# Flight_Track_V2.net
KiCad netlist of a schematic drawn in EasyEDA Pro
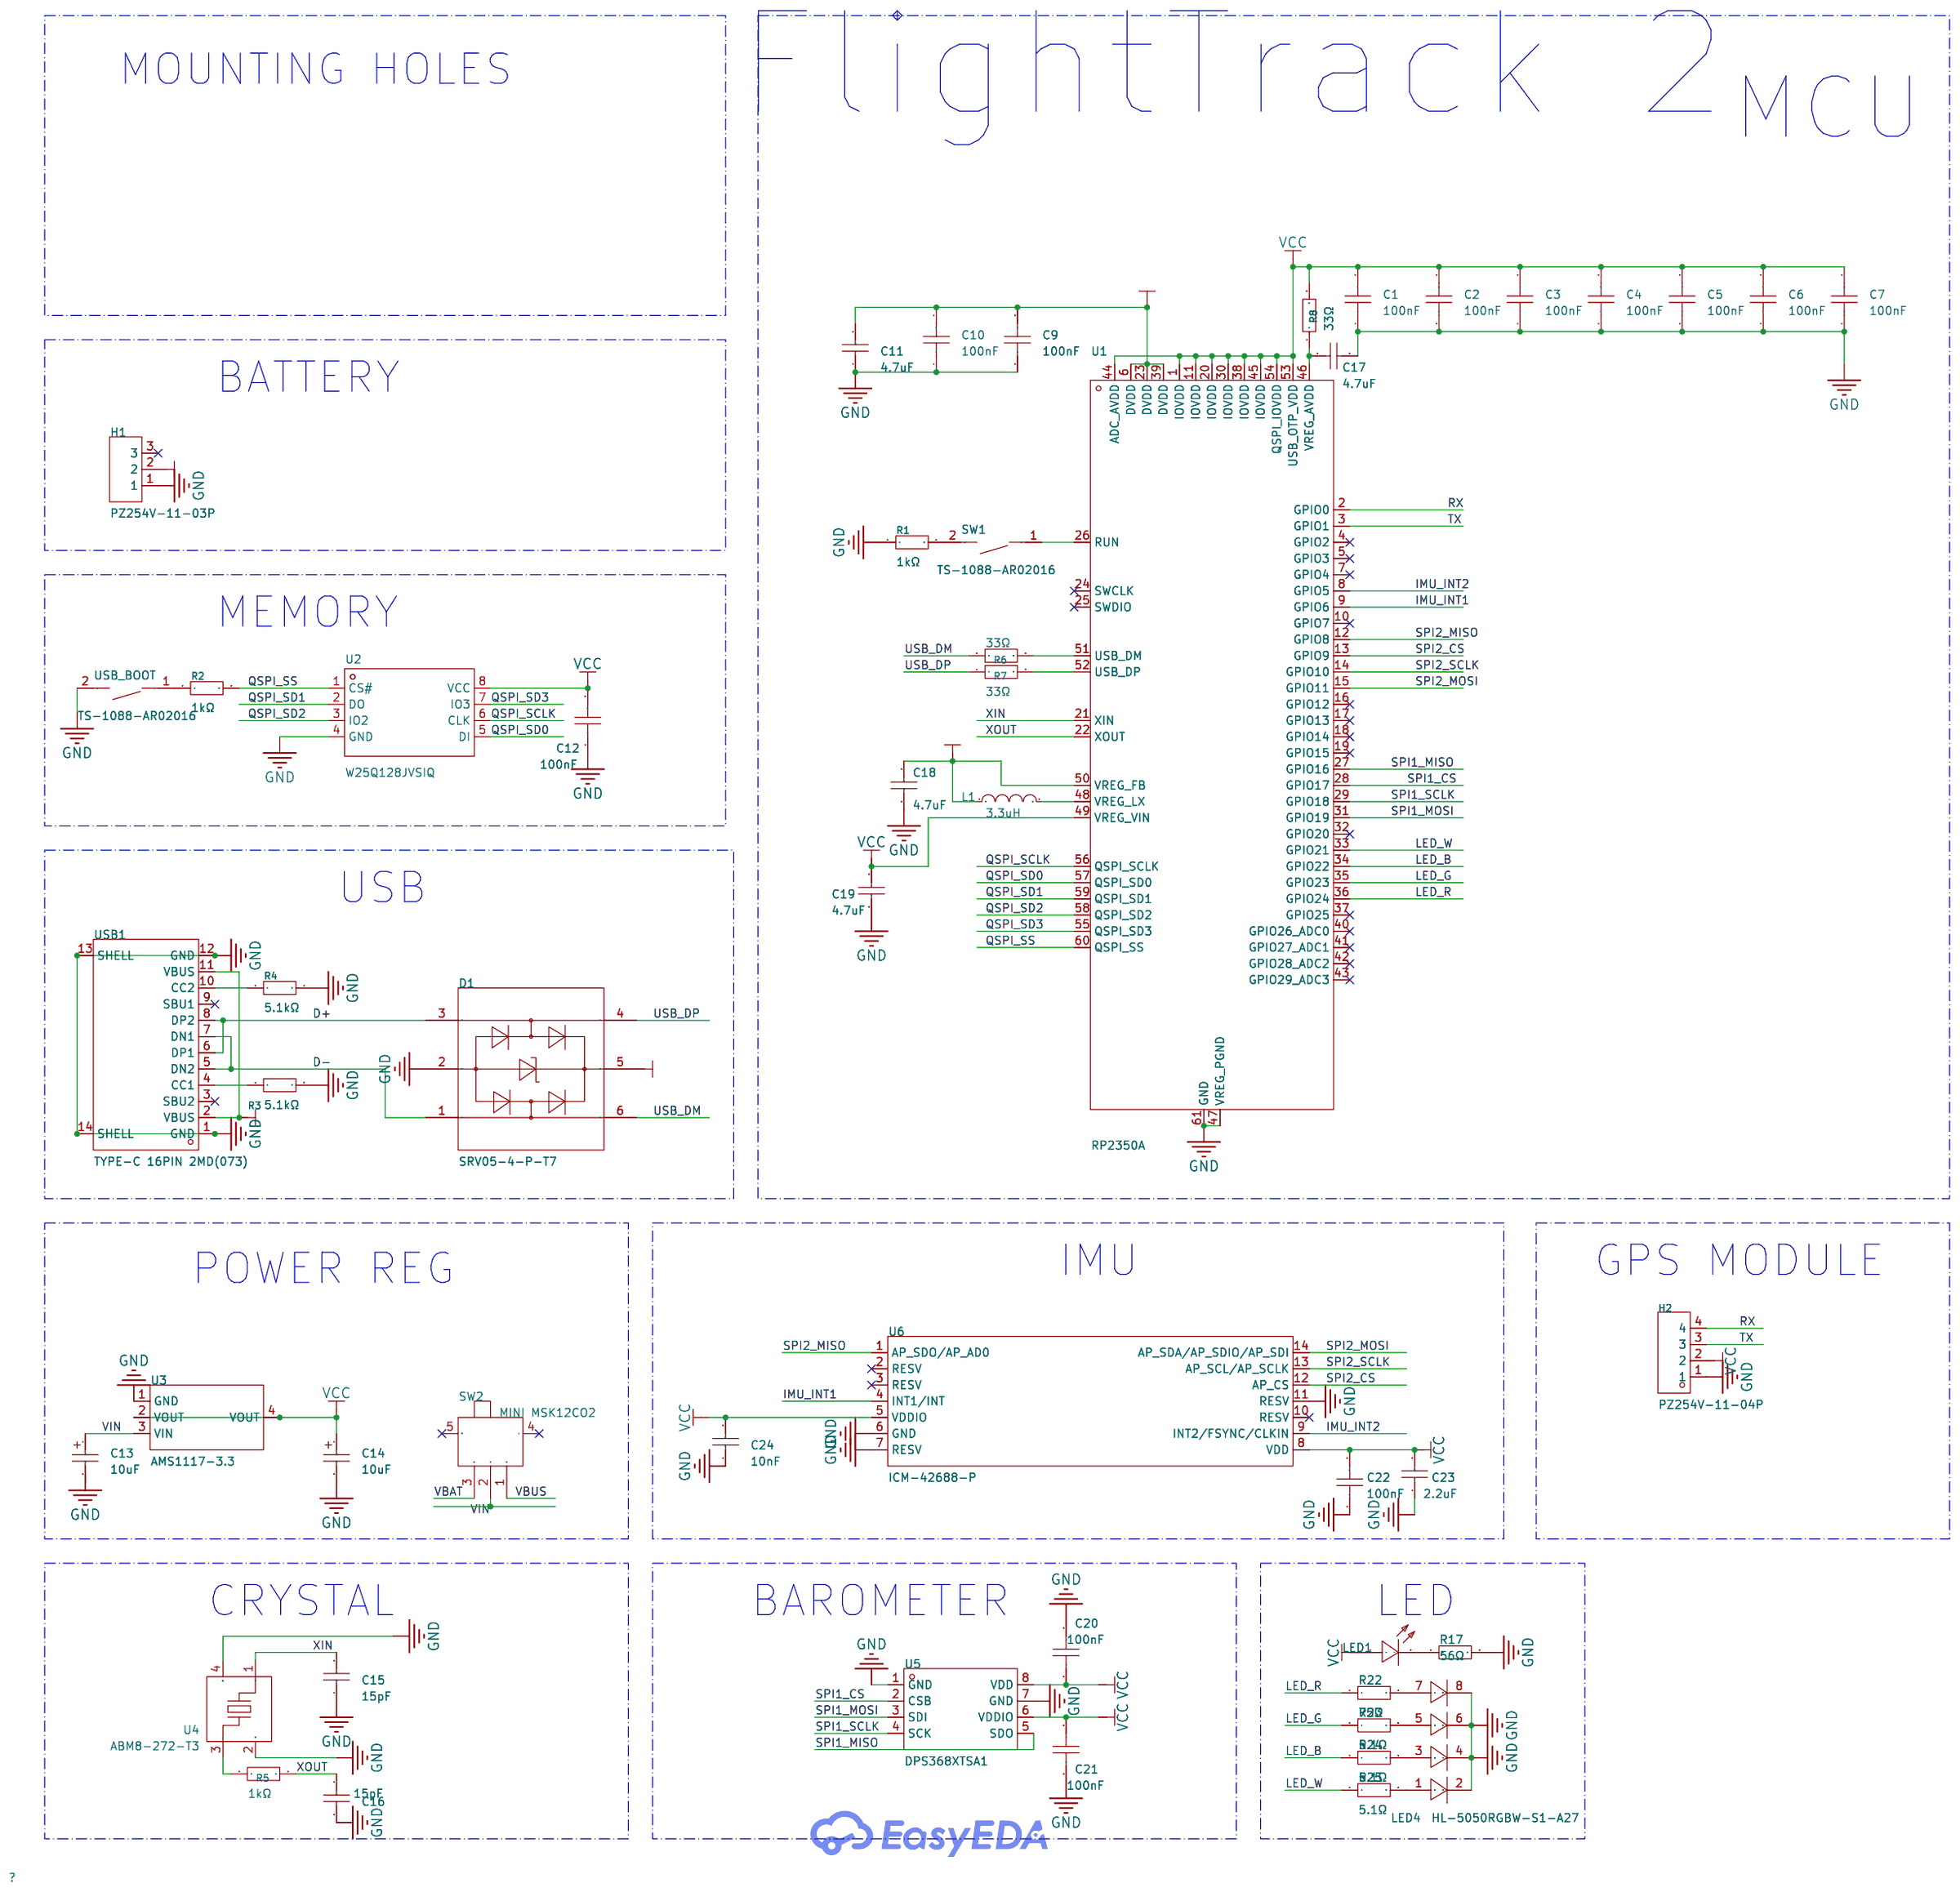
[diagram p0: schematic sheet]

(export (version "E")
  (design (tool "Eeschema 10.0.6"))
  (components
    (comp (ref "C1")
      (value "100nF")
      (footprint "easyedapro:C0402")
      (fields
        (field (name "Manufacturer Part") "CL05B104KO5NNNC")
        (field (name "Manufacturer") "SAMSUNG(三星)")
      )
      (libsource (lib "easyedapro") (part "CL05B104KO5NNNC"))
    )
    (comp (ref "C2")
      (value "100nF")
      (footprint "easyedapro:C0402")
      (fields
        (field (name "Manufacturer Part") "CL05B104KO5NNNC")
        (field (name "Manufacturer") "SAMSUNG(三星)")
      )
      (libsource (lib "easyedapro") (part "CL05B104KO5NNNC"))
    )
    (comp (ref "C3")
      (value "100nF")
      (footprint "easyedapro:C0402")
      (fields
        (field (name "Manufacturer Part") "CL05B104KO5NNNC")
        (field (name "Manufacturer") "SAMSUNG(三星)")
      )
      (libsource (lib "easyedapro") (part "CL05B104KO5NNNC"))
    )
    (comp (ref "C4")
      (value "100nF")
      (footprint "easyedapro:C0402")
      (fields
        (field (name "Manufacturer Part") "CL05B104KO5NNNC")
        (field (name "Manufacturer") "SAMSUNG(三星)")
      )
      (libsource (lib "easyedapro") (part "CL05B104KO5NNNC"))
    )
    (comp (ref "C5")
      (value "100nF")
      (footprint "easyedapro:C0402")
      (fields
        (field (name "Manufacturer Part") "CL05B104KO5NNNC")
        (field (name "Manufacturer") "SAMSUNG(三星)")
      )
      (libsource (lib "easyedapro") (part "CL05B104KO5NNNC"))
    )
    (comp (ref "C6")
      (value "100nF")
      (footprint "easyedapro:C0402")
      (fields
        (field (name "Manufacturer Part") "CL05B104KO5NNNC")
        (field (name "Manufacturer") "SAMSUNG(三星)")
      )
      (libsource (lib "easyedapro") (part "CL05B104KO5NNNC"))
    )
    (comp (ref "C7")
      (value "100nF")
      (footprint "easyedapro:C0402")
      (fields
        (field (name "Manufacturer Part") "CL05B104KO5NNNC")
        (field (name "Manufacturer") "SAMSUNG(三星)")
      )
      (libsource (lib "easyedapro") (part "CL05B104KO5NNNC"))
    )
    (comp (ref "C9")
      (value "100nF")
      (footprint "easyedapro:C0402")
      (fields
        (field (name "Manufacturer Part") "CL05B104KO5NNNC")
        (field (name "Manufacturer") "SAMSUNG(三星)")
      )
      (libsource (lib "easyedapro") (part "CL05B104KO5NNNC"))
    )
    (comp (ref "C10")
      (value "100nF")
      (footprint "easyedapro:C0402")
      (fields
        (field (name "Manufacturer Part") "CL05B104KO5NNNC")
        (field (name "Manufacturer") "SAMSUNG(三星)")
      )
      (libsource (lib "easyedapro") (part "CL05B104KO5NNNC"))
    )
    (comp (ref "C11")
      (value "4.7uF")
      (footprint "easyedapro:C0805")
      (fields
        (field (name "Manufacturer Part") "CL21A475KAQNNNE")
        (field (name "Manufacturer") "SAMSUNG(三星)")
      )
      (libsource (lib "easyedapro") (part "CL21A475KAQNNNE"))
    )
    (comp (ref "C12")
      (value "100nF")
      (footprint "easyedapro:C0603")
      (description "Capacitance:100nF Tolerance:±10% Tolerance:±10% Voltage Rating:50V Temperature Coefficient:X7R")
      (fields
        (field (name "Manufacturer Part") "CC0603KRX7R9BB104")
        (field (name "Manufacturer") "YAGEO(国巨)")
      )
      (libsource (lib "easyedapro") (part "CC0603KRX7R9BB104"))
    )
    (comp (ref "C13")
      (value "10uF")
      (footprint "easyedapro:CAP-SMD_L3.2-W1.6-RD-C7171")
      (fields (field (name "Manufacturer Part") "TAJA106K016RNJ") (field (name "Manufacturer") "Kyocera AVX"))
      (libsource (lib "easyedapro") (part "TAJA106K016RNJ"))
    )
    (comp (ref "C14")
      (value "10uF")
      (footprint "easyedapro:CAP-SMD_L3.2-W1.6-RD-C7171")
      (fields (field (name "Manufacturer Part") "TAJA106K016RNJ") (field (name "Manufacturer") "Kyocera AVX"))
      (libsource (lib "easyedapro") (part "TAJA106K016RNJ"))
    )
    (comp (ref "C15")
      (value "15pF")
      (footprint "easyedapro:C0402")
      (fields (field (name "Manufacturer Part") "0402CG150J500NT") (field (name "Manufacturer") "FH(风华)"))
      (libsource (lib "easyedapro") (part "0402CG150J500NT"))
    )
    (comp (ref "C16")
      (value "15pF")
      (footprint "easyedapro:C0402")
      (fields (field (name "Manufacturer Part") "0402CG150J500NT") (field (name "Manufacturer") "FH(风华)"))
      (libsource (lib "easyedapro") (part "0402CG150J500NT"))
    )
    (comp (ref "C17")
      (value "4.7uF")
      (footprint "easyedapro:C0805")
      (fields
        (field (name "Manufacturer Part") "CL21A475KAQNNNE")
        (field (name "Manufacturer") "SAMSUNG(三星)")
      )
      (libsource (lib "easyedapro") (part "CL21A475KAQNNNE"))
    )
    (comp (ref "C18")
      (value "4.7uF")
      (footprint "easyedapro:C0805")
      (fields
        (field (name "Manufacturer Part") "CL21A475KAQNNNE")
        (field (name "Manufacturer") "SAMSUNG(三星)")
      )
      (libsource (lib "easyedapro") (part "CL21A475KAQNNNE"))
    )
    (comp (ref "C19")
      (value "4.7uF")
      (footprint "easyedapro:C0805")
      (fields
        (field (name "Manufacturer Part") "CL21A475KAQNNNE")
        (field (name "Manufacturer") "SAMSUNG(三星)")
      )
      (libsource (lib "easyedapro") (part "CL21A475KAQNNNE"))
    )
    (comp (ref "C20")
      (value "100nF")
      (footprint "easyedapro:C0402")
      (fields
        (field (name "Manufacturer Part") "CL05B104KO5NNNC")
        (field (name "Manufacturer") "SAMSUNG(三星)")
      )
      (libsource (lib "easyedapro") (part "CL05B104KO5NNNC"))
    )
    (comp (ref "C21")
      (value "100nF")
      (footprint "easyedapro:C0402")
      (fields
        (field (name "Manufacturer Part") "CL05B104KO5NNNC")
        (field (name "Manufacturer") "SAMSUNG(三星)")
      )
      (libsource (lib "easyedapro") (part "CL05B104KO5NNNC"))
    )
    (comp (ref "C22")
      (value "100nF")
      (footprint "easyedapro:C0402")
      (fields
        (field (name "Manufacturer Part") "CL05B104KO5NNNC")
        (field (name "Manufacturer") "SAMSUNG(三星)")
      )
      (libsource (lib "easyedapro") (part "CL05B104KO5NNNC"))
    )
    (comp (ref "C23")
      (value "2.2uF")
      (footprint "easyedapro:C0603")
      (fields
        (field (name "Manufacturer Part") "CL10A225KO8NNNC")
        (field (name "Manufacturer") "SAMSUNG(三星)")
      )
      (libsource (lib "easyedapro") (part "CL10A225KO8NNNC"))
    )
    (comp (ref "C24")
      (value "10nF")
      (footprint "easyedapro:C0402")
      (fields
        (field (name "Manufacturer Part") "CL05B103KB5NNNC")
        (field (name "Manufacturer") "SAMSUNG(三星)")
      )
      (libsource (lib "easyedapro") (part "CL05B103KB5NNNC"))
    )
    (comp (ref "D1")
      (value "SRV05-4-P-T7")
      (footprint "easyedapro:SOT-23-6_L2.9-W1.6-P0.95-LS2.8-BL")
      (fields (field (name "Manufacturer") "TECH PUBLIC(台舟)"))
      (libsource (lib "easyedapro") (part "USBLC6-2SC6"))
    )
    (comp (ref "H1")
      (value "PZ254V-11-03P")
      (footprint "easyedapro:HDR-TH_3P-P2.54-V-M")
      (fields (field (name "Manufacturer") "XFCN(兴飞)"))
      (libsource (lib "easyedapro") (part "PZ254V-11-03P_C2937625"))
    )
    (comp (ref "H2")
      (value "PZ254V-11-04P")
      (footprint "easyedapro:HDR-TH_4P-P2.54-V-M")
      (fields (field (name "Manufacturer") "XFCN(兴飞)"))
      (libsource (lib "easyedapro") (part "PZ254V-11-04P_C2691448"))
    )
    (comp (ref "L1")
      (value "3.3uH")
      (footprint "easyedapro:L0603")
      (fields (field (name "Manufacturer Part") "CMI160808U3R3KT") (field (name "Manufacturer") "FH(风华)"))
      (libsource (lib "easyedapro") (part "CMI160808U3R3KT"))
    )
    (comp (ref "LED1")
      (value "NCD0805R1")
      (footprint "easyedapro:LED0805-R-RD")
      (fields (field (name "Manufacturer") "国星光电"))
      (libsource (lib "easyedapro") (part "FC-2012HRK-620D"))
    )
    (comp (ref "LED4")
      (value "HL-5050RGBW-S1-A27")
      (footprint "easyedapro:LED-SMD_8P-L5.0-W5.0-P1.20_HL-5050RGBW-S1-A27")
      (fields (field (name "Manufacturer") "HONGLITRONIC(鸿利光电)"))
      (libsource (lib "easyedapro") (part "HL-5050RGBW-S1-A27"))
    )
    (comp (ref "R1")
      (value "1kΩ")
      (footprint "easyedapro:R0402")
      (fields
        (field (name "Manufacturer Part") "0402WGF1001TCE")
        (field (name "Manufacturer") "UNI-ROYAL(厚声)")
      )
      (libsource (lib "easyedapro") (part "0402WGF1001TCE"))
    )
    (comp (ref "R2")
      (value "1kΩ")
      (footprint "easyedapro:R0402")
      (fields
        (field (name "Manufacturer Part") "0402WGF1001TCE")
        (field (name "Manufacturer") "UNI-ROYAL(厚声)")
      )
      (libsource (lib "easyedapro") (part "0402WGF1001TCE"))
    )
    (comp (ref "R3")
      (value "5.1kΩ")
      (footprint "easyedapro:R0402")
      (fields
        (field (name "Manufacturer Part") "0402WGF5101TCE")
        (field (name "Manufacturer") "UNI-ROYAL(厚声)")
      )
      (libsource (lib "easyedapro") (part "0402WGF5101TCE"))
    )
    (comp (ref "R4")
      (value "5.1kΩ")
      (footprint "easyedapro:R0402")
      (fields
        (field (name "Manufacturer Part") "0402WGF5101TCE")
        (field (name "Manufacturer") "UNI-ROYAL(厚声)")
      )
      (libsource (lib "easyedapro") (part "0402WGF5101TCE"))
    )
    (comp (ref "R5")
      (value "1kΩ")
      (footprint "easyedapro:R0402")
      (fields
        (field (name "Manufacturer Part") "0402WGF1001TCE")
        (field (name "Manufacturer") "UNI-ROYAL(厚声)")
      )
      (libsource (lib "easyedapro") (part "0402WGF1001TCE"))
    )
    (comp (ref "R6")
      (value "33Ω")
      (footprint "easyedapro:R0402")
      (fields
        (field (name "Manufacturer Part") "0402WGF330JTCE")
        (field (name "Manufacturer") "UNI-ROYAL(厚声)")
      )
      (libsource (lib "easyedapro") (part "0402WGF330JTCE"))
    )
    (comp (ref "R7")
      (value "33Ω")
      (footprint "easyedapro:R0402")
      (fields
        (field (name "Manufacturer Part") "0402WGF330JTCE")
        (field (name "Manufacturer") "UNI-ROYAL(厚声)")
      )
      (libsource (lib "easyedapro") (part "0402WGF330JTCE"))
    )
    (comp (ref "R8")
      (value "33Ω")
      (footprint "easyedapro:R0402")
      (fields
        (field (name "Manufacturer Part") "0402WGF330JTCE")
        (field (name "Manufacturer") "UNI-ROYAL(厚声)")
      )
      (libsource (lib "easyedapro") (part "0402WGF330JTCE"))
    )
    (comp (ref "R17")
      (value "56Ω")
      (footprint "easyedapro:R0603")
      (fields
        (field (name "Manufacturer Part") "0603WAF560JT5E")
        (field (name "Manufacturer") "UNI-ROYAL(厚声)")
      )
      (libsource (lib "easyedapro") (part "0603WAF560JT5E"))
    )
    (comp (ref "R22")
      (value "75Ω")
      (footprint "easyedapro:R0603")
      (fields
        (field (name "Manufacturer Part") "0603WAF750JT5E")
        (field (name "Manufacturer") "UNI-ROYAL(厚声)")
      )
      (libsource (lib "easyedapro") (part "0603WAF750JT5E"))
    )
    (comp (ref "R23")
      (value "5.1Ω")
      (footprint "easyedapro:R0603")
      (fields
        (field (name "Manufacturer Part") "0603WAF510KT5E")
        (field (name "Manufacturer") "UNI-ROYAL(厚声)")
      )
      (libsource (lib "easyedapro") (part "0603WAF510KT5E"))
    )
    (comp (ref "R24")
      (value "5.1Ω")
      (footprint "easyedapro:R0603")
      (fields
        (field (name "Manufacturer Part") "0603WAF510KT5E")
        (field (name "Manufacturer") "UNI-ROYAL(厚声)")
      )
      (libsource (lib "easyedapro") (part "0603WAF510KT5E"))
    )
    (comp (ref "R25")
      (value "5.1Ω")
      (footprint "easyedapro:R0603")
      (fields
        (field (name "Manufacturer Part") "0603WAF510KT5E")
        (field (name "Manufacturer") "UNI-ROYAL(厚声)")
      )
      (libsource (lib "easyedapro") (part "0603WAF510KT5E"))
    )
    (comp (ref "SW1")
      (value "TS-1088-AR02016")
      (footprint "easyedapro:SW-SMD_L3.9-W3.0-P4.45")
      (fields (field (name "Manufacturer") "XUNPU(讯普)"))
      (libsource (lib "easyedapro") (part "TS-1088-AR02016"))
    )
    (comp (ref "SW2")
      (value "MINI MSK12CO2")
      (footprint "easyedapro:SW-SMD_MSK12CO2")
      (fields (field (name "Manufacturer") "SHOU HAN(首韩)"))
      (libsource (lib "easyedapro") (part "MINI MSK12CO2"))
    )
    (comp (ref "U1")
      (value "RP2350A")
      (footprint "easyedapro:QFN-60_L7.0-W7.0-P0.40-TL-EP3.4")
      (fields (field (name "Manufacturer") "Raspberry Pi(树莓派)"))
      (libsource (lib "easyedapro") (part "RP2350A_C42411118"))
    )
    (comp (ref "U2")
      (value "W25Q128JVSIQ")
      (footprint "easyedapro:SOIC-8_L5.3-W5.3-P1.27-LS8.0-BL")
      (fields (field (name "Manufacturer") "WINBOND(华邦)"))
      (libsource (lib "easyedapro") (part "W25Q128JVSIQTR"))
    )
    (comp (ref "U3")
      (value "AMS1117-3.3")
      (footprint "easyedapro:SOT-223-3_L6.5-W3.4-P2.30-LS7.0-BR")
      (fields (field (name "Manufacturer") "AMS"))
      (libsource (lib "easyedapro") (part "AMS1117-3.3"))
    )
    (comp (ref "U4")
      (value "ABM8-272-T3")
      (footprint "easyedapro:CRYSTAL-SMD_4P-L3.2-W2.5-BL")
      (fields (field (name "Manufacturer") "ABRACON"))
      (libsource (lib "easyedapro") (part "ABM8-272-T3_C20625731"))
    )
    (comp (ref "U5")
      (value "DPS368XTSA1")
      (footprint "easyedapro:LGA-8_L2.5-W2.0-P0.65-TR_DPS368")
      (fields (field (name "Manufacturer") "Infineon(英飞凌)"))
      (libsource (lib "easyedapro") (part "DPS368XTSA1"))
    )
    (comp (ref "U6")
      (value "ICM-42688-P")
      (footprint "easyedapro:LGA-14_L3.0-W2.5-P0.50-TL")
      (description "Sensor Type:Accelerometer gyroscope")
      (fields (field (name "Manufacturer") "TDK InvenSense(应美盛)"))
      (libsource (lib "easyedapro") (part "ICM-42688-P"))
    )
    (comp (ref "USB1")
      (value "TYPE-C 16PIN 2MD(073)")
      (footprint "easyedapro:USB-C-SMD_TYPE-C-6PIN-2MD-073")
      (fields (field (name "Manufacturer") "SHOU HAN(首韩)"))
      (libsource (lib "easyedapro") (part "TYPE-C 16PIN 2MD(073)"))
    )
    (comp (ref "USB_BOOT")
      (value "TS-1088-AR02016")
      (footprint "easyedapro:SW-SMD_L3.9-W3.0-P4.45")
      (fields (field (name "Manufacturer") "XUNPU(讯普)"))
      (libsource (lib "easyedapro") (part "TS-1088-AR02016"))
    )
  )
  (nets
    (net (code "1") (name "/D+") (class "Default")
      (node (ref "D1") (pin "3") (pinfunction "3_3") (pintype "input"))
      (node (ref "USB1") (pin "6") (pinfunction "DP1_6") (pintype "unspecified"))
      (node (ref "USB1") (pin "8") (pinfunction "DP2_8") (pintype "unspecified"))
    )
    (net (code "2") (name "/D-") (class "Default")
      (node (ref "D1") (pin "1") (pinfunction "1_1") (pintype "input"))
      (node (ref "USB1") (pin "5") (pinfunction "DN2_5") (pintype "unspecified"))
      (node (ref "USB1") (pin "7") (pinfunction "DN1_7") (pintype "unspecified"))
    )
    (net (code "3") (name "/IMU_INT1") (class "Default")
      (node (ref "U1") (pin "9") (pinfunction "GPIO6_9") (pintype "unspecified"))
      (node (ref "U6") (pin "4") (pinfunction "INT1/INT_4") (pintype "unspecified"))
    )
    (net (code "4") (name "/IMU_INT2") (class "Default")
      (node (ref "U1") (pin "8") (pinfunction "GPIO5_8") (pintype "unspecified"))
      (node (ref "U6") (pin "9") (pinfunction "INT2/FSYNC/CLKIN_9") (pintype "unspecified"))
    )
    (net (code "5") (name "/LED_B") (class "Default")
      (node (ref "R24") (pin "1") (pinfunction "1_1") (pintype "input"))
      (node (ref "U1") (pin "34") (pinfunction "GPIO22_34") (pintype "unspecified"))
    )
    (net (code "6") (name "/LED_G") (class "Default")
      (node (ref "R23") (pin "1") (pinfunction "1_1") (pintype "input"))
      (node (ref "U1") (pin "35") (pinfunction "GPIO23_35") (pintype "unspecified"))
    )
    (net (code "7") (name "/LED_R") (class "Default")
      (node (ref "R22") (pin "1") (pinfunction "1_1") (pintype "input"))
      (node (ref "U1") (pin "36") (pinfunction "GPIO24_36") (pintype "unspecified"))
    )
    (net (code "8") (name "/LED_W") (class "Default")
      (node (ref "R25") (pin "1") (pinfunction "1_1") (pintype "input"))
      (node (ref "U1") (pin "33") (pinfunction "GPIO21_33") (pintype "unspecified"))
    )
    (net (code "9") (name "/QSPI_SCLK") (class "Default")
      (node (ref "U1") (pin "56") (pinfunction "QSPI_SCLK_56") (pintype "unspecified"))
      (node (ref "U2") (pin "6") (pinfunction "CLK_6") (pintype "unspecified"))
    )
    (net (code "10") (name "/QSPI_SD0") (class "Default")
      (node (ref "U1") (pin "57") (pinfunction "QSPI_SD0_57") (pintype "unspecified"))
      (node (ref "U2") (pin "5") (pinfunction "DI_5") (pintype "unspecified"))
    )
    (net (code "11") (name "/QSPI_SD1") (class "Default")
      (node (ref "U1") (pin "59") (pinfunction "QSPI_SD1_59") (pintype "unspecified"))
      (node (ref "U2") (pin "2") (pinfunction "DO_2") (pintype "unspecified"))
    )
    (net (code "12") (name "/QSPI_SD2") (class "Default")
      (node (ref "U1") (pin "58") (pinfunction "QSPI_SD2_58") (pintype "unspecified"))
      (node (ref "U2") (pin "3") (pinfunction "IO2_3") (pintype "unspecified"))
    )
    (net (code "13") (name "/QSPI_SD3") (class "Default")
      (node (ref "U1") (pin "55") (pinfunction "QSPI_SD3_55") (pintype "unspecified"))
      (node (ref "U2") (pin "7") (pinfunction "IO3_7") (pintype "unspecified"))
    )
    (net (code "14") (name "/QSPI_SS") (class "Default")
      (node (ref "R2") (pin "2") (pinfunction "2_2") (pintype "input"))
      (node (ref "U1") (pin "60") (pinfunction "QSPI_SS_60") (pintype "unspecified"))
      (node (ref "U2") (pin "1") (pinfunction "CS#_1") (pintype "unspecified"))
    )
    (net (code "15") (name "/RX") (class "Default")
      (node (ref "H2") (pin "4") (pinfunction "4_4") (pintype "input"))
      (node (ref "U1") (pin "2") (pinfunction "GPIO0_2") (pintype "unspecified"))
    )
    (net (code "16") (name "/SPI1_CS") (class "Default")
      (node (ref "U1") (pin "28") (pinfunction "GPIO17_28") (pintype "unspecified"))
      (node (ref "U5") (pin "2") (pinfunction "CSB_2") (pintype "unspecified"))
    )
    (net (code "17") (name "/SPI1_MISO") (class "Default")
      (node (ref "U1") (pin "27") (pinfunction "GPIO16_27") (pintype "unspecified"))
      (node (ref "U5") (pin "5") (pinfunction "SDO_5") (pintype "unspecified"))
    )
    (net (code "18") (name "/SPI1_MOSI") (class "Default")
      (node (ref "U1") (pin "31") (pinfunction "GPIO19_31") (pintype "unspecified"))
      (node (ref "U5") (pin "3") (pinfunction "SDI_3") (pintype "unspecified"))
    )
    (net (code "19") (name "/SPI1_SCLK") (class "Default")
      (node (ref "U1") (pin "29") (pinfunction "GPIO18_29") (pintype "unspecified"))
      (node (ref "U5") (pin "4") (pinfunction "SCK_4") (pintype "unspecified"))
    )
    (net (code "20") (name "/SPI2_CS") (class "Default")
      (node (ref "U1") (pin "13") (pinfunction "GPIO9_13") (pintype "unspecified"))
      (node (ref "U6") (pin "12") (pinfunction "AP_CS_12") (pintype "unspecified"))
    )
    (net (code "21") (name "/SPI2_MISO") (class "Default")
      (node (ref "U1") (pin "12") (pinfunction "GPIO8_12") (pintype "unspecified"))
      (node (ref "U6") (pin "1") (pinfunction "AP_SDO/AP_AD0_1") (pintype "unspecified"))
    )
    (net (code "22") (name "/SPI2_MOSI") (class "Default")
      (node (ref "U1") (pin "15") (pinfunction "GPIO11_15") (pintype "unspecified"))
      (node (ref "U6") (pin "14") (pinfunction "AP_SDA/AP_SDIO/AP_SDI_14") (pintype "unspecified"))
    )
    (net (code "23") (name "/SPI2_SCLK") (class "Default")
      (node (ref "U1") (pin "14") (pinfunction "GPIO10_14") (pintype "unspecified"))
      (node (ref "U6") (pin "13") (pinfunction "AP_SCL/AP_SCLK_13") (pintype "unspecified"))
    )
    (net (code "24") (name "/TX") (class "Default")
      (node (ref "H2") (pin "3") (pinfunction "3_3") (pintype "input"))
      (node (ref "U1") (pin "3") (pinfunction "GPIO1_3") (pintype "unspecified"))
    )
    (net (code "25") (name "/USB_DM") (class "Default")
      (node (ref "D1") (pin "6") (pinfunction "6_6") (pintype "input"))
      (node (ref "R6") (pin "1") (pinfunction "1_1") (pintype "input"))
    )
    (net (code "26") (name "/USB_DP") (class "Default")
      (node (ref "D1") (pin "4") (pinfunction "4_4") (pintype "input"))
      (node (ref "R7") (pin "1") (pinfunction "1_1") (pintype "input"))
    )
    (net (code "27") (name "/VIN") (class "Default")
      (node (ref "C13") (pin "1") (pinfunction "1_1") (pintype "input"))
      (node (ref "SW2") (pin "2") (pinfunction "2_2") (pintype "unspecified"))
      (node (ref "U3") (pin "3") (pinfunction "VIN_3") (pintype "unspecified"))
    )
    (net (code "28") (name "/XIN") (class "Default")
      (node (ref "C15") (pin "2") (pinfunction "2_2") (pintype "input"))
      (node (ref "U1") (pin "21") (pinfunction "XIN_21") (pintype "unspecified"))
      (node (ref "U4") (pin "1") (pinfunction "1_1") (pintype "input"))
    )
    (net (code "29") (name "/XOUT") (class "Default")
      (node (ref "C16") (pin "2") (pinfunction "2_2") (pintype "input"))
      (node (ref "R5") (pin "2") (pinfunction "2_2") (pintype "input"))
      (node (ref "U1") (pin "22") (pinfunction "XOUT_22") (pintype "unspecified"))
    )
    (net (code "30") (name "1V1") (class "Default")
      (node (ref "C10") (pin "2") (pinfunction "2_2") (pintype "unspecified"))
      (node (ref "C11") (pin "2") (pinfunction "2_2") (pintype "input"))
      (node (ref "C18") (pin "2") (pinfunction "2_2") (pintype "input"))
      (node (ref "C9") (pin "2") (pinfunction "2_2") (pintype "unspecified"))
      (node (ref "L1") (pin "1") (pinfunction "1_1") (pintype "unspecified"))
      (node (ref "U1") (pin "23") (pinfunction "DVDD_23") (pintype "unspecified"))
      (node (ref "U1") (pin "39") (pinfunction "DVDD_39") (pintype "unspecified"))
      (node (ref "U1") (pin "50") (pinfunction "VREG_FB_50") (pintype "unspecified"))
      (node (ref "U1") (pin "6") (pinfunction "DVDD_6") (pintype "unspecified"))
    )
    (net (code "31") (name "GND") (class "Default")
      (node (ref "C1") (pin "1") (pinfunction "1_1") (pintype "unspecified"))
      (node (ref "C10") (pin "1") (pinfunction "1_1") (pintype "unspecified"))
      (node (ref "C11") (pin "1") (pinfunction "1_1") (pintype "input"))
      (node (ref "C12") (pin "1") (pinfunction "1_1") (pintype "unspecified"))
      (node (ref "C13") (pin "2") (pinfunction "2_2") (pintype "input"))
      (node (ref "C14") (pin "2") (pinfunction "2_2") (pintype "input"))
      (node (ref "C15") (pin "1") (pinfunction "1_1") (pintype "input"))
      (node (ref "C16") (pin "1") (pinfunction "1_1") (pintype "input"))
      (node (ref "C17") (pin "2") (pinfunction "2_2") (pintype "input"))
      (node (ref "C18") (pin "1") (pinfunction "1_1") (pintype "input"))
      (node (ref "C19") (pin "1") (pinfunction "1_1") (pintype "input"))
      (node (ref "C2") (pin "1") (pinfunction "1_1") (pintype "unspecified"))
      (node (ref "C20") (pin "2") (pinfunction "2_2") (pintype "unspecified"))
      (node (ref "C21") (pin "1") (pinfunction "1_1") (pintype "unspecified"))
      (node (ref "C22") (pin "1") (pinfunction "1_1") (pintype "unspecified"))
      (node (ref "C23") (pin "1") (pinfunction "1_1") (pintype "input"))
      (node (ref "C24") (pin "1") (pinfunction "1_1") (pintype "input"))
      (node (ref "C3") (pin "1") (pinfunction "1_1") (pintype "unspecified"))
      (node (ref "C4") (pin "1") (pinfunction "1_1") (pintype "unspecified"))
      (node (ref "C5") (pin "1") (pinfunction "1_1") (pintype "unspecified"))
      (node (ref "C6") (pin "1") (pinfunction "1_1") (pintype "unspecified"))
      (node (ref "C7") (pin "1") (pinfunction "1_1") (pintype "unspecified"))
      (node (ref "C9") (pin "1") (pinfunction "1_1") (pintype "unspecified"))
      (node (ref "D1") (pin "2") (pinfunction "2_2") (pintype "input"))
      (node (ref "H1") (pin "1") (pinfunction "1_1") (pintype "unspecified"))
      (node (ref "H2") (pin "1") (pinfunction "1_1") (pintype "input"))
      (node (ref "LED4") (pin "2") (pinfunction "2_2") (pintype "unspecified"))
      (node (ref "LED4") (pin "4") (pinfunction "4_4") (pintype "unspecified"))
      (node (ref "LED4") (pin "6") (pinfunction "6_6") (pintype "unspecified"))
      (node (ref "LED4") (pin "8") (pinfunction "8_8") (pintype "unspecified"))
      (node (ref "R1") (pin "1") (pinfunction "1_1") (pintype "input"))
      (node (ref "R17") (pin "2") (pinfunction "2_2") (pintype "input"))
      (node (ref "R3") (pin "2") (pinfunction "2_2") (pintype "input"))
      (node (ref "R4") (pin "2") (pinfunction "2_2") (pintype "input"))
      (node (ref "U1") (pin "47") (pinfunction "VREG_PGND_47") (pintype "unspecified"))
      (node (ref "U1") (pin "61") (pinfunction "GND_61") (pintype "unspecified"))
      (node (ref "U2") (pin "4") (pinfunction "GND_4") (pintype "unspecified"))
      (node (ref "U3") (pin "1") (pinfunction "GND_1") (pintype "unspecified"))
      (node (ref "U4") (pin "2") (pinfunction "GND_2") (pintype "input"))
      (node (ref "U4") (pin "4") (pinfunction "GND_4") (pintype "input"))
      (node (ref "U5") (pin "1") (pinfunction "GND_1") (pintype "unspecified"))
      (node (ref "U5") (pin "7") (pinfunction "GND_7") (pintype "unspecified"))
      (node (ref "U6") (pin "11") (pinfunction "RESV_11") (pintype "unspecified"))
      (node (ref "U6") (pin "6") (pinfunction "GND_6") (pintype "unspecified"))
      (node (ref "U6") (pin "7") (pinfunction "RESV_7") (pintype "unspecified"))
      (node (ref "USB1") (pin "1") (pinfunction "GND_1") (pintype "unspecified"))
      (node (ref "USB1") (pin "12") (pinfunction "GND_12") (pintype "unspecified"))
      (node (ref "USB1") (pin "13") (pinfunction "SHELL_13") (pintype "unspecified"))
      (node (ref "USB1") (pin "14") (pinfunction "SHELL_14") (pintype "unspecified"))
      (node (ref "USB_BOOT") (pin "2") (pinfunction "2_2") (pintype "unspecified"))
    )
    (net (code "32") (name "Net-(LED1--)") (class "Default")
      (node (ref "LED1") (pin "2") (pinfunction "-_2") (pintype "unspecified"))
      (node (ref "R17") (pin "1") (pinfunction "1_1") (pintype "input"))
    )
    (net (code "33") (name "Net-(LED4-Pad1)") (class "Default")
      (node (ref "LED4") (pin "1") (pinfunction "1_1") (pintype "unspecified"))
      (node (ref "R25") (pin "2") (pinfunction "2_2") (pintype "input"))
    )
    (net (code "34") (name "Net-(LED4-Pad3)") (class "Default")
      (node (ref "LED4") (pin "3") (pinfunction "3_3") (pintype "unspecified"))
      (node (ref "R24") (pin "2") (pinfunction "2_2") (pintype "input"))
    )
    (net (code "35") (name "Net-(LED4-Pad5)") (class "Default")
      (node (ref "LED4") (pin "5") (pinfunction "5_5") (pintype "unspecified"))
      (node (ref "R23") (pin "2") (pinfunction "2_2") (pintype "input"))
    )
    (net (code "36") (name "Net-(LED4-Pad7)") (class "Default")
      (node (ref "LED4") (pin "7") (pinfunction "7_7") (pintype "unspecified"))
      (node (ref "R22") (pin "2") (pinfunction "2_2") (pintype "input"))
    )
    (net (code "37") (name "Net-(R1-Pad2)") (class "Default")
      (node (ref "R1") (pin "2") (pinfunction "2_2") (pintype "input"))
      (node (ref "SW1") (pin "2") (pinfunction "2_2") (pintype "unspecified"))
    )
    (net (code "38") (name "Net-(R2-Pad1)") (class "Default")
      (node (ref "R2") (pin "1") (pinfunction "1_1") (pintype "input"))
      (node (ref "USB_BOOT") (pin "1") (pinfunction "1_1") (pintype "unspecified"))
    )
    (net (code "39") (name "Net-(R5-Pad1)") (class "Default")
      (node (ref "R5") (pin "1") (pinfunction "1_1") (pintype "input"))
      (node (ref "U4") (pin "3") (pinfunction "3_3") (pintype "input"))
    )
    (net (code "40") (name "Net-(U1-RUN)") (class "Default")
      (node (ref "SW1") (pin "1") (pinfunction "1_1") (pintype "unspecified"))
      (node (ref "U1") (pin "26") (pinfunction "RUN_26") (pintype "unspecified"))
    )
    (net (code "41") (name "Net-(U1-USB_DM)") (class "Default")
      (node (ref "R6") (pin "2") (pinfunction "2_2") (pintype "input"))
      (node (ref "U1") (pin "51") (pinfunction "USB_DM_51") (pintype "unspecified"))
    )
    (net (code "42") (name "Net-(U1-USB_DP)") (class "Default")
      (node (ref "R7") (pin "2") (pinfunction "2_2") (pintype "input"))
      (node (ref "U1") (pin "52") (pinfunction "USB_DP_52") (pintype "unspecified"))
    )
    (net (code "43") (name "Net-(U1-VREG_AVDD)") (class "Default")
      (node (ref "C17") (pin "1") (pinfunction "1_1") (pintype "input"))
      (node (ref "R8") (pin "1") (pinfunction "1_1") (pintype "input"))
      (node (ref "U1") (pin "46") (pinfunction "VREG_AVDD_46") (pintype "unspecified"))
    )
    (net (code "44") (name "Net-(U1-VREG_LX)") (class "Default")
      (node (ref "L1") (pin "2") (pinfunction "2_2") (pintype "unspecified"))
      (node (ref "U1") (pin "48") (pinfunction "VREG_LX_48") (pintype "unspecified"))
    )
    (net (code "45") (name "Net-(USB1-CC1)") (class "Default")
      (node (ref "R3") (pin "1") (pinfunction "1_1") (pintype "input"))
      (node (ref "USB1") (pin "4") (pinfunction "CC1_4") (pintype "unspecified"))
    )
    (net (code "46") (name "Net-(USB1-CC2)") (class "Default")
      (node (ref "R4") (pin "1") (pinfunction "1_1") (pintype "input"))
      (node (ref "USB1") (pin "10") (pinfunction "CC2_10") (pintype "unspecified"))
    )
    (net (code "47") (name "VBAT") (class "Default")
      (node (ref "H1") (pin "2") (pinfunction "2_2") (pintype "unspecified"))
      (node (ref "SW2") (pin "3") (pinfunction "3_3") (pintype "unspecified"))
    )
    (net (code "48") (name "VBUS") (class "Default")
      (node (ref "D1") (pin "5") (pinfunction "5_5") (pintype "input"))
      (node (ref "SW2") (pin "1") (pinfunction "1_1") (pintype "unspecified"))
      (node (ref "USB1") (pin "11") (pinfunction "VBUS_11") (pintype "unspecified"))
      (node (ref "USB1") (pin "2") (pinfunction "VBUS_2") (pintype "unspecified"))
    )
    (net (code "49") (name "VCC") (class "Default")
      (node (ref "C1") (pin "2") (pinfunction "2_2") (pintype "unspecified"))
      (node (ref "C12") (pin "2") (pinfunction "2_2") (pintype "unspecified"))
      (node (ref "C14") (pin "1") (pinfunction "1_1") (pintype "input"))
      (node (ref "C19") (pin "2") (pinfunction "2_2") (pintype "input"))
      (node (ref "C2") (pin "2") (pinfunction "2_2") (pintype "unspecified"))
      (node (ref "C20") (pin "1") (pinfunction "1_1") (pintype "unspecified"))
      (node (ref "C21") (pin "2") (pinfunction "2_2") (pintype "unspecified"))
      (node (ref "C22") (pin "2") (pinfunction "2_2") (pintype "unspecified"))
      (node (ref "C23") (pin "2") (pinfunction "2_2") (pintype "input"))
      (node (ref "C24") (pin "2") (pinfunction "2_2") (pintype "input"))
      (node (ref "C3") (pin "2") (pinfunction "2_2") (pintype "unspecified"))
      (node (ref "C4") (pin "2") (pinfunction "2_2") (pintype "unspecified"))
      (node (ref "C5") (pin "2") (pinfunction "2_2") (pintype "unspecified"))
      (node (ref "C6") (pin "2") (pinfunction "2_2") (pintype "unspecified"))
      (node (ref "C7") (pin "2") (pinfunction "2_2") (pintype "unspecified"))
      (node (ref "H2") (pin "2") (pinfunction "2_2") (pintype "input"))
      (node (ref "LED1") (pin "1") (pinfunction "+_1") (pintype "unspecified"))
      (node (ref "R8") (pin "2") (pinfunction "2_2") (pintype "input"))
      (node (ref "U1") (pin "1") (pinfunction "IOVDD_1") (pintype "unspecified"))
      (node (ref "U1") (pin "11") (pinfunction "IOVDD_11") (pintype "unspecified"))
      (node (ref "U1") (pin "20") (pinfunction "IOVDD_20") (pintype "unspecified"))
      (node (ref "U1") (pin "30") (pinfunction "IOVDD_30") (pintype "unspecified"))
      (node (ref "U1") (pin "38") (pinfunction "IOVDD_38") (pintype "unspecified"))
      (node (ref "U1") (pin "44") (pinfunction "ADC_AVDD_44") (pintype "unspecified"))
      (node (ref "U1") (pin "45") (pinfunction "IOVDD_45") (pintype "unspecified"))
      (node (ref "U1") (pin "49") (pinfunction "VREG_VIN_49") (pintype "unspecified"))
      (node (ref "U1") (pin "53") (pinfunction "USB_OTP_VDD_53") (pintype "unspecified"))
      (node (ref "U1") (pin "54") (pinfunction "QSPI_IOVDD_54") (pintype "unspecified"))
      (node (ref "U2") (pin "8") (pinfunction "VCC_8") (pintype "unspecified"))
      (node (ref "U3") (pin "2") (pinfunction "VOUT_2") (pintype "unspecified"))
      (node (ref "U3") (pin "4") (pinfunction "VOUT_4") (pintype "unspecified"))
      (node (ref "U5") (pin "6") (pinfunction "VDDIO_6") (pintype "unspecified"))
      (node (ref "U5") (pin "8") (pinfunction "VDD_8") (pintype "unspecified"))
      (node (ref "U6") (pin "5") (pinfunction "VDDIO_5") (pintype "unspecified"))
      (node (ref "U6") (pin "8") (pinfunction "VDD_8") (pintype "unspecified"))
    )
    (net (code "50") (name "unconnected-(H1-Pad3)") (class "Default")
      (node (ref "H1") (pin "3") (pinfunction "3_3") (pintype "unspecified+no_connect"))
    )
    (net (code "51") (name "unconnected-(SW2-Pad4)") (class "Default")
      (node (ref "SW2") (pin "4") (pinfunction "4_4") (pintype "unspecified+no_connect"))
    )
    (net (code "52") (name "unconnected-(SW2-Pad5)") (class "Default")
      (node (ref "SW2") (pin "5") (pinfunction "5_5") (pintype "unspecified+no_connect"))
    )
    (net (code "53") (name "unconnected-(U1-GPIO2-Pad4)") (class "Default")
      (node (ref "U1") (pin "4") (pinfunction "GPIO2_4") (pintype "unspecified+no_connect"))
    )
    (net (code "54") (name "unconnected-(U1-GPIO3-Pad5)") (class "Default")
      (node (ref "U1") (pin "5") (pinfunction "GPIO3_5") (pintype "unspecified+no_connect"))
    )
    (net (code "55") (name "unconnected-(U1-GPIO4-Pad7)") (class "Default")
      (node (ref "U1") (pin "7") (pinfunction "GPIO4_7") (pintype "unspecified+no_connect"))
    )
    (net (code "56") (name "unconnected-(U1-GPIO7-Pad10)") (class "Default")
      (node (ref "U1") (pin "10") (pinfunction "GPIO7_10") (pintype "unspecified+no_connect"))
    )
    (net (code "57") (name "unconnected-(U1-GPIO12-Pad16)") (class "Default")
      (node (ref "U1") (pin "16") (pinfunction "GPIO12_16") (pintype "unspecified+no_connect"))
    )
    (net (code "58") (name "unconnected-(U1-GPIO13-Pad17)") (class "Default")
      (node (ref "U1") (pin "17") (pinfunction "GPIO13_17") (pintype "unspecified+no_connect"))
    )
    (net (code "59") (name "unconnected-(U1-GPIO14-Pad18)") (class "Default")
      (node (ref "U1") (pin "18") (pinfunction "GPIO14_18") (pintype "unspecified+no_connect"))
    )
    (net (code "60") (name "unconnected-(U1-GPIO15-Pad19)") (class "Default")
      (node (ref "U1") (pin "19") (pinfunction "GPIO15_19") (pintype "unspecified+no_connect"))
    )
    (net (code "61") (name "unconnected-(U1-GPIO20-Pad32)") (class "Default")
      (node (ref "U1") (pin "32") (pinfunction "GPIO20_32") (pintype "unspecified+no_connect"))
    )
    (net (code "62") (name "unconnected-(U1-GPIO25-Pad37)") (class "Default")
      (node (ref "U1") (pin "37") (pinfunction "GPIO25_37") (pintype "unspecified+no_connect"))
    )
    (net (code "63") (name "unconnected-(U1-GPIO26_ADC0-Pad40)") (class "Default")
      (node (ref "U1") (pin "40") (pinfunction "GPIO26_ADC0_40") (pintype "unspecified+no_connect"))
    )
    (net (code "64") (name "unconnected-(U1-GPIO27_ADC1-Pad41)") (class "Default")
      (node (ref "U1") (pin "41") (pinfunction "GPIO27_ADC1_41") (pintype "unspecified+no_connect"))
    )
    (net (code "65") (name "unconnected-(U1-GPIO28_ADC2-Pad42)") (class "Default")
      (node (ref "U1") (pin "42") (pinfunction "GPIO28_ADC2_42") (pintype "unspecified+no_connect"))
    )
    (net (code "66") (name "unconnected-(U1-GPIO29_ADC3-Pad43)") (class "Default")
      (node (ref "U1") (pin "43") (pinfunction "GPIO29_ADC3_43") (pintype "unspecified+no_connect"))
    )
    (net (code "67") (name "unconnected-(U1-SWCLK-Pad24)") (class "Default")
      (node (ref "U1") (pin "24") (pinfunction "SWCLK_24") (pintype "unspecified+no_connect"))
    )
    (net (code "68") (name "unconnected-(U1-SWDIO-Pad25)") (class "Default")
      (node (ref "U1") (pin "25") (pinfunction "SWDIO_25") (pintype "unspecified+no_connect"))
    )
    (net (code "69") (name "unconnected-(U6-RESV-Pad2)") (class "Default")
      (node (ref "U6") (pin "2") (pinfunction "RESV_2") (pintype "unspecified+no_connect"))
    )
    (net (code "70") (name "unconnected-(U6-RESV-Pad3)") (class "Default")
      (node (ref "U6") (pin "3") (pinfunction "RESV_3") (pintype "unspecified+no_connect"))
    )
    (net (code "71") (name "unconnected-(U6-RESV-Pad10)") (class "Default")
      (node (ref "U6") (pin "10") (pinfunction "RESV_10") (pintype "unspecified+no_connect"))
    )
    (net (code "72") (name "unconnected-(USB1-SBU1-Pad9)") (class "Default")
      (node (ref "USB1") (pin "9") (pinfunction "SBU1_9") (pintype "unspecified+no_connect"))
    )
    (net (code "73") (name "unconnected-(USB1-SBU2-Pad3)") (class "Default")
      (node (ref "USB1") (pin "3") (pinfunction "SBU2_3") (pintype "unspecified+no_connect"))
    )
  )
)
